# 51shiyanban.net
KiCad netlist of a schematic drawn in Altium Designer
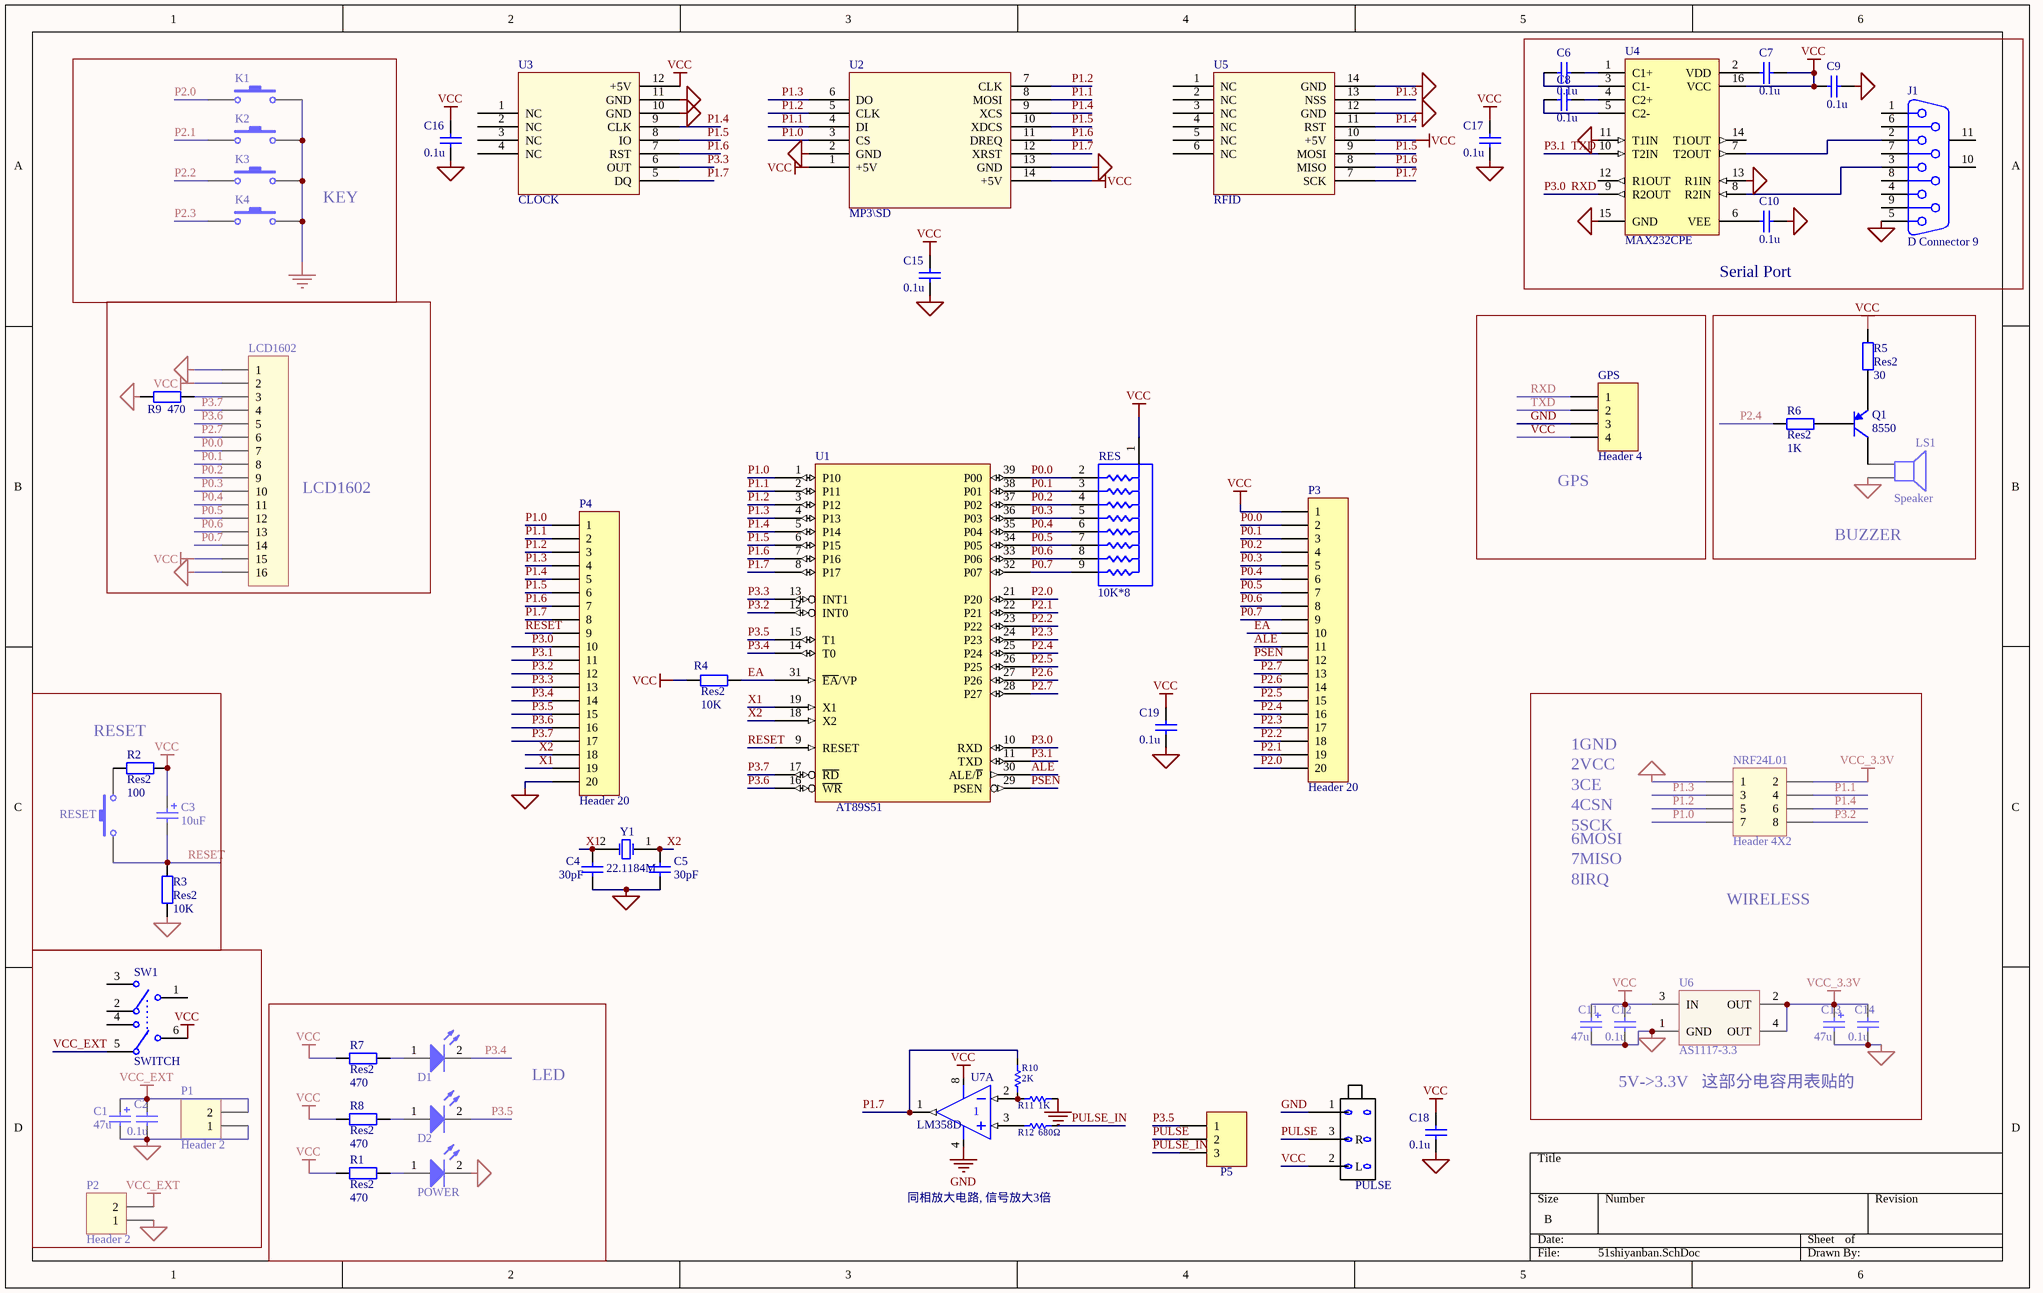
[diagram p0: 51shiyanban.SchDoc]

(export (version "E")
  (design (tool "Eeschema 10.0.6"))
  (components
    (comp (ref "C1")
      (value "47u")
      (footprint "CAP3_HT")
      (description "Polarized Capacitor (Radial)")
      (fields
        (field (name "MANUFACTURER") "Generic Components")
        (field (name "Comment") "Cap Pol1")
        (field (name "PUBLISHER") "Altium Hobart Technology Centre")
      )
      (libsource (lib "Miscellaneous Devices") (part "Cap Pol1"))
    )
    (comp (ref "C2")
      (value "0.1u")
      (footprint "CAP1_HT")
      (description "Capacitor")
      (fields
        (field (name "MANUFACTURER") "Generic Components")
        (field (name "PUBLISHER") "Altium Hobart Technology Centre")
      )
      (libsource (lib "") (part "Cap_1"))
    )
    (comp (ref "C3")
      (value "10uF")
      (footprint "CAP3_HT")
      (description "Polarized Capacitor (Radial)")
      (fields
        (field (name "MANUFACTURER") "Generic Components")
        (field (name "Comment") "Cap Pol1")
        (field (name "PUBLISHER") "Altium Hobart Technology Centre")
      )
      (libsource (lib "Miscellaneous Devices") (part "Cap Pol1"))
    )
    (comp (ref "C4")
      (value "30pF")
      (footprint "CAP1_HT")
      (description "Capacitor")
      (fields
        (field (name "MANUFACTURER") "Generic Components")
        (field (name "Comment") "30P")
        (field (name "PUBLISHER") "Altium Hobart Technology Centre")
      )
      (libsource (lib "") (part "Cap_1"))
    )
    (comp (ref "C5")
      (value "30pF")
      (footprint "CAP1_HT")
      (description "Capacitor")
      (fields
        (field (name "MANUFACTURER") "Generic Components")
        (field (name "Comment") "30P")
        (field (name "PUBLISHER") "Altium Hobart Technology Centre")
      )
      (libsource (lib "") (part "Cap_1"))
    )
    (comp (ref "C6")
      (value "0.1u")
      (footprint "CAP1_HT")
      (description "Capacitor")
      (fields
        (field (name "MANUFACTURER") "Generic Components")
        (field (name "PUBLISHER") "Altium Hobart Technology Centre")
      )
      (libsource (lib "Miscellaneous Devices") (part "Cap"))
    )
    (comp (ref "C7")
      (value "0.1u")
      (footprint "CAP1_HT")
      (description "Capacitor")
      (fields
        (field (name "MANUFACTURER") "Generic Components")
        (field (name "PUBLISHER") "Altium Hobart Technology Centre")
      )
      (libsource (lib "Miscellaneous Devices") (part "Cap"))
    )
    (comp (ref "C8")
      (value "0.1u")
      (footprint "CAP1_HT")
      (description "Capacitor")
      (fields
        (field (name "MANUFACTURER") "Generic Components")
        (field (name "PUBLISHER") "Altium Hobart Technology Centre")
      )
      (libsource (lib "Miscellaneous Devices") (part "Cap"))
    )
    (comp (ref "C9")
      (value "0.1u")
      (footprint "CAP1_HT")
      (description "Capacitor")
      (fields
        (field (name "MANUFACTURER") "Generic Components")
        (field (name "PUBLISHER") "Altium Hobart Technology Centre")
      )
      (libsource (lib "Miscellaneous Devices") (part "Cap"))
    )
    (comp (ref "C10")
      (value "0.1u")
      (footprint "CAP1_HT")
      (description "Capacitor")
      (fields
        (field (name "MANUFACTURER") "Generic Components")
        (field (name "PUBLISHER") "Altium Hobart Technology Centre")
      )
      (libsource (lib "Miscellaneous Devices") (part "Cap"))
    )
    (comp (ref "C11")
      (value "47u")
      (footprint "CAP_CA_D")
      (description "Polarized Capacitor (Radial)")
      (fields
        (field (name "MANUFACTURER") "Generic Components")
        (field (name "PUBLISHER") "Altium Hobart Technology Centre")
      )
      (libsource (lib "Miscellaneous Devices") (part "Cap Pol1"))
    )
    (comp (ref "C12")
      (value "0.1u")
      (footprint "C0805")
      (description "Capacitor")
      (fields
        (field (name "MANUFACTURER") "Generic Components")
        (field (name "PUBLISHER") "Altium Hobart Technology Centre")
      )
      (libsource (lib "") (part "Cap_1"))
    )
    (comp (ref "C13")
      (value "47u")
      (footprint "CAP_CA_D")
      (description "Polarized Capacitor (Radial)")
      (fields
        (field (name "MANUFACTURER") "Generic Components")
        (field (name "PUBLISHER") "Altium Hobart Technology Centre")
      )
      (libsource (lib "Miscellaneous Devices") (part "Cap Pol1"))
    )
    (comp (ref "C14")
      (value "0.1u")
      (footprint "C0805")
      (description "Capacitor")
      (fields
        (field (name "MANUFACTURER") "Generic Components")
        (field (name "PUBLISHER") "Altium Hobart Technology Centre")
      )
      (libsource (lib "") (part "Cap_1"))
    )
    (comp (ref "C15")
      (value "0.1u")
      (footprint "C0805")
      (description "Capacitor")
      (fields
        (field (name "MANUFACTURER") "Generic Components")
        (field (name "PUBLISHER") "Altium Hobart Technology Centre")
      )
      (libsource (lib "") (part "Cap_1"))
    )
    (comp (ref "C16")
      (value "0.1u")
      (footprint "C0805")
      (description "Capacitor")
      (fields
        (field (name "MANUFACTURER") "Generic Components")
        (field (name "PUBLISHER") "Altium Hobart Technology Centre")
      )
      (libsource (lib "") (part "Cap_1"))
    )
    (comp (ref "C17")
      (value "0.1u")
      (footprint "C0805")
      (description "Capacitor")
      (fields
        (field (name "MANUFACTURER") "Generic Components")
        (field (name "PUBLISHER") "Altium Hobart Technology Centre")
      )
      (libsource (lib "") (part "Cap_1"))
    )
    (comp (ref "C18")
      (value "0.1u")
      (footprint "C0805")
      (description "Capacitor")
      (fields
        (field (name "MANUFACTURER") "Generic Components")
        (field (name "PUBLISHER") "Altium Hobart Technology Centre")
      )
      (libsource (lib "") (part "Cap_1"))
    )
    (comp (ref "C19")
      (value "0.1u")
      (footprint "C0805")
      (description "Capacitor")
      (fields
        (field (name "MANUFACTURER") "Generic Components")
        (field (name "PUBLISHER") "Altium Hobart Technology Centre")
      )
      (libsource (lib "") (part "Cap_1"))
    )
    (comp (ref "D1")
      (value "LED0")
      (footprint "LED1_HT")
      (description "Typical INFRARED GaAs LED")
      (fields
        (field (name "MANUFACTURER") "Generic Components")
        (field (name "PUBLISHER") "Altium Hobart Technology Centre")
      )
      (libsource (lib "Miscellaneous Devices") (part "LED0"))
    )
    (comp (ref "D2")
      (value "LED0")
      (footprint "LED1_HT")
      (description "Typical INFRARED GaAs LED")
      (fields
        (field (name "MANUFACTURER") "Generic Components")
        (field (name "PUBLISHER") "Altium Hobart Technology Centre")
      )
      (libsource (lib "Miscellaneous Devices") (part "LED0"))
    )
    (comp (ref "GPS")
      (value "Header 4")
      (footprint "HDR1X4")
      (description "Header, 4-Pin")
      (fields (field (name "PUBLISHER") "Altium Limited"))
      (libsource (lib "Miscellaneous Connectors") (part "Header 4"))
    )
    (comp (ref "J1")
      (value "D Connector 9")
      (footprint "DSUB1.385-2H9")
      (description "Receptacle Assembly, 9 Position, Right Angle")
      (fields (field (name "PUBLISHER") "Altium Limited"))
      (libsource (lib "Miscellaneous Connectors") (part "D Connector 9"))
    )
    (comp (ref "K1")
      (value "~")
      (footprint "KEY1_HT")
      (description "Switch")
      (fields (field (name "MANUFACTURER") "Generic Components"))
      (libsource (lib "Miscellaneous Devices") (part "SW-PB"))
    )
    (comp (ref "K2")
      (value "~")
      (footprint "KEY1_HT")
      (description "Switch")
      (fields (field (name "MANUFACTURER") "Generic Components"))
      (libsource (lib "Miscellaneous Devices") (part "SW-PB"))
    )
    (comp (ref "K3")
      (value "~")
      (footprint "KEY1_HT")
      (description "Switch")
      (fields (field (name "MANUFACTURER") "Generic Components"))
      (libsource (lib "Miscellaneous Devices") (part "SW-PB"))
    )
    (comp (ref "K4")
      (value "~")
      (footprint "KEY1_HT")
      (description "Switch")
      (fields (field (name "MANUFACTURER") "Generic Components"))
      (libsource (lib "Miscellaneous Devices") (part "SW-PB"))
    )
    (comp (ref "LCD1602")
      (value "Header 16")
      (footprint "HDR1X16")
      (description "Header, 16-Pin")
      (fields (field (name "PUBLISHER") "Altium Limited"))
      (libsource (lib "Miscellaneous Connectors") (part "Header 16"))
    )
    (comp (ref "LS1")
      (value "Speaker")
      (footprint "BUZZER_HT")
      (description "Loudspeaker")
      (fields (field (name "MANUFACTURER") "Generic Components"))
      (libsource (lib "Miscellaneous Devices") (part "Speaker"))
    )
    (comp (ref "NRF24L01")
      (value "Header 4X2")
      (footprint "HDR2X4")
      (description "Header, 4-Pin, Dual row")
      (fields (field (name "PUBLISHER") "Altium Limited"))
      (libsource (lib "Miscellaneous Connectors") (part "Header 4X2"))
    )
    (comp (ref "P1")
      (value "Header 2")
      (footprint "DCJACK")
      (description "Header, 2-Pin")
      (fields (field (name "MANUFACTURER") "Generic Components"))
      (libsource (lib "Miscellaneous Connectors") (part "Header 2"))
    )
    (comp (ref "P2")
      (value "Header 2")
      (footprint "Power_small")
      (description "Header, 2-Pin")
      (fields (field (name "MANUFACTURER") "Generic Components"))
      (libsource (lib "Miscellaneous Connectors") (part "Header 2"))
    )
    (comp (ref "P3")
      (value "Header 20")
      (footprint "HDR1X20")
      (description "Header, 20-Pin")
      (fields (field (name "PUBLISHER") "Altium Limited"))
      (libsource (lib "Miscellaneous Connectors") (part "Header 20"))
    )
    (comp (ref "P4")
      (value "Header 20")
      (footprint "HDR1X20")
      (description "Header, 20-Pin")
      (fields (field (name "PUBLISHER") "Altium Limited"))
      (libsource (lib "Miscellaneous Connectors") (part "Header 20"))
    )
    (comp (ref "P5")
      (value "Header 3")
      (footprint "HDR1X3")
      (description "Header, 3-Pin")
      (fields (field (name "PUBLISHER") "Altium Limited"))
      (libsource (lib "Miscellaneous Connectors") (part "Header 3"))
    )
    (comp (ref "POWER")
      (value "LED0")
      (footprint "LED1_HT")
      (description "Typical INFRARED GaAs LED")
      (fields
        (field (name "MANUFACTURER") "Generic Components")
        (field (name "PUBLISHER") "Altium Hobart Technology Centre")
      )
      (libsource (lib "Miscellaneous Devices") (part "LED0"))
    )
    (comp (ref "PULSE")
      (value "Phonejack")
      (footprint "3.5mmphonejack")
      (libsource (lib "MyLib") (part "Phonejack"))
    )
    (comp (ref "Q1")
      (value "8550")
      (footprint "Transistor")
      (description "PNP General Purpose Amplifier")
      (fields (field (name "PUBLISHER") "Altium Limited"))
      (libsource (lib "Miscellaneous Devices") (part "2N3906"))
    )
    (comp (ref "R1")
      (value "Res2")
      (footprint "AXIAL-0.4")
      (description "Resistor")
      (fields (field (name "ALTIUM_VALUE") "470") (field (name "PUBLISHER") "Altium Limited"))
      (libsource (lib "Miscellaneous Devices") (part "Res2"))
    )
    (comp (ref "R2")
      (value "Res2")
      (footprint "AXIAL-0.4")
      (description "Resistor")
      (fields (field (name "ALTIUM_VALUE") "100") (field (name "PUBLISHER") "Altium Limited"))
      (libsource (lib "") (part "Res2_2"))
    )
    (comp (ref "R3")
      (value "Res2")
      (footprint "AXIAL-0.4")
      (description "Resistor")
      (fields (field (name "ALTIUM_VALUE") "10K") (field (name "PUBLISHER") "Altium Limited"))
      (libsource (lib "") (part "Res2_1"))
    )
    (comp (ref "R4")
      (value "Res2")
      (footprint "AXIAL-0.4")
      (description "Resistor")
      (fields (field (name "ALTIUM_VALUE") "10K") (field (name "PUBLISHER") "Altium Limited"))
      (libsource (lib "") (part "Res2_2"))
    )
    (comp (ref "R5")
      (value "Res2")
      (footprint "AXIAL-0.4")
      (description "Resistor")
      (fields (field (name "ALTIUM_VALUE") "30") (field (name "PUBLISHER") "Altium Limited"))
      (libsource (lib "") (part "Res2_3"))
    )
    (comp (ref "R6")
      (value "Res2")
      (footprint "AXIAL-0.4")
      (description "Resistor")
      (fields (field (name "ALTIUM_VALUE") "1K") (field (name "PUBLISHER") "Altium Limited"))
      (libsource (lib "") (part "Res2_2"))
    )
    (comp (ref "R7")
      (value "Res2")
      (footprint "AXIAL-0.4")
      (description "Resistor")
      (fields (field (name "ALTIUM_VALUE") "470") (field (name "PUBLISHER") "Altium Limited"))
      (libsource (lib "Miscellaneous Devices") (part "Res2"))
    )
    (comp (ref "R8")
      (value "Res2")
      (footprint "AXIAL-0.4")
      (description "Resistor")
      (fields (field (name "ALTIUM_VALUE") "470") (field (name "PUBLISHER") "Altium Limited"))
      (libsource (lib "Miscellaneous Devices") (part "Res2"))
    )
    (comp (ref "R9")
      (value "470")
      (footprint "AXIAL-0.4")
      (description "Resistor")
      (fields (field (name "Comment") "Res2") (field (name "PUBLISHER") "Altium Limited"))
      (libsource (lib "") (part "Res2_2"))
    )
    (comp (ref "R10")
      (value "2K")
      (footprint "C0805")
      (description "Resistor")
      (fields (field (name "PUBLISHER") "Altium Limited"))
      (libsource (lib "Miscellaneous Devices") (part "Res1"))
    )
    (comp (ref "R11")
      (value "1K")
      (footprint "C0805")
      (description "Resistor")
      (fields (field (name "PUBLISHER") "Altium Limited"))
      (libsource (lib "Miscellaneous Devices") (part "Res1"))
    )
    (comp (ref "R12")
      (value "680Ω")
      (footprint "C0805")
      (description "Resistor")
      (fields (field (name "PUBLISHER") "Altium Limited"))
      (libsource (lib "Miscellaneous Devices") (part "Res1"))
    )
    (comp (ref "RES") (value "10K*8") (footprint "RES3_HT") (libsource (lib "Schlib1") (part "RESPACK")))
    (comp (ref "RESET")
      (value "~")
      (footprint "KEY1_HT")
      (description "Switch")
      (fields (field (name "MANUFACTURER") "Generic Components"))
      (libsource (lib "Miscellaneous Devices") (part "SW-PB"))
    )
    (comp (ref "SW1") (value "SWITCH") (footprint "DPDT-6") (libsource (lib "WENSHI") (part "SW-DPDT")))
    (comp (ref "U1") (value "AT89S51") (footprint "KDIP40_HT") (libsource (lib "*") (part "8031")))
    (comp (ref "U2") (value "MP~{3}SD") (footprint "MP3SD") (libsource (lib "Schlib1") (part "MP3SD")))
    (comp (ref "U3") (value "CLOCK") (footprint "CLOCK") (libsource (lib "Schlib1") (part "CLOCK")))
    (comp (ref "U4")
      (value "MAX232CPE")
      (footprint "DIP-16")
      (description "+5V Powered RS-232 Driver/Receiver")
      (fields (field (name "PUBLISHER") "Altium Limited"))
      (libsource (lib "Maxim Communication Transceiver") (part "MAX232CPE"))
    )
    (comp (ref "U5") (value "RFID") (footprint "RFID") (libsource (lib "Schlib1") (part "RFID")))
    (comp (ref "U6")
      (value "AS1117-3.3")
      (footprint "SOT-223")
      (libsource (lib "WENSHI") (part "AS1117-3.3"))
    )
    (comp (ref "U7")
      (value "LM358D")
      (footprint "751-02_N")
      (description "Dual Low-Power Operational Amplifier")
      (fields (field (name "PUBLISHER") "Altium Limited"))
      (libsource (lib "Motorola Amplifier Operational Amplifier") (part "LM358D"))
    )
    (comp (ref "Y1")
      (value "22.1184M")
      (footprint "XTAL1_HT")
      (description "Crystal Oscillator")
      (fields
        (field (name "MANUFACTURER") "Generic Components")
        (field (name "PUBLISHER") "Altium Hobart Technology Centre")
      )
      (libsource (lib "Miscellaneous Devices") (part "XTAL"))
    )
  )
  (nets
    (net (code "1") (name "/ALE") (class "Default")
      (node (ref "P3") (pin "11") (pinfunction "11_11") (pintype "passive"))
      (node (ref "U1") (pin "30") (pinfunction "ALE/~{P}_30") (pintype "output"))
    )
    (net (code "2") (name "/EA") (class "Default")
      (node (ref "P3") (pin "10") (pinfunction "10_10") (pintype "passive"))
      (node (ref "R4") (pin "1") (pinfunction "1_1") (pintype "passive"))
      (node (ref "U1") (pin "31") (pinfunction "~{EA}/VP_31") (pintype "input"))
    )
    (net (code "3") (name "/P0.0") (class "Default")
      (node (ref "LCD1602") (pin "7") (pinfunction "7_7") (pintype "passive"))
      (node (ref "P3") (pin "2") (pinfunction "2_2") (pintype "passive"))
      (node (ref "RES") (pin "2") (pinfunction "2_2") (pintype "passive"))
      (node (ref "U1") (pin "39") (pinfunction "P00_39") (pintype "bidirectional"))
    )
    (net (code "4") (name "/P0.1") (class "Default")
      (node (ref "LCD1602") (pin "8") (pinfunction "8_8") (pintype "passive"))
      (node (ref "P3") (pin "3") (pinfunction "3_3") (pintype "passive"))
      (node (ref "RES") (pin "3") (pinfunction "3_3") (pintype "passive"))
      (node (ref "U1") (pin "38") (pinfunction "P01_38") (pintype "bidirectional"))
    )
    (net (code "5") (name "/P0.2") (class "Default")
      (node (ref "LCD1602") (pin "9") (pinfunction "9_9") (pintype "passive"))
      (node (ref "P3") (pin "4") (pinfunction "4_4") (pintype "passive"))
      (node (ref "RES") (pin "4") (pinfunction "4_4") (pintype "passive"))
      (node (ref "U1") (pin "37") (pinfunction "P02_37") (pintype "bidirectional"))
    )
    (net (code "6") (name "/P0.3") (class "Default")
      (node (ref "LCD1602") (pin "10") (pinfunction "10_10") (pintype "passive"))
      (node (ref "P3") (pin "5") (pinfunction "5_5") (pintype "passive"))
      (node (ref "RES") (pin "5") (pinfunction "5_5") (pintype "passive"))
      (node (ref "U1") (pin "36") (pinfunction "P03_36") (pintype "bidirectional"))
    )
    (net (code "7") (name "/P0.4") (class "Default")
      (node (ref "LCD1602") (pin "11") (pinfunction "11_11") (pintype "passive"))
      (node (ref "P3") (pin "6") (pinfunction "6_6") (pintype "passive"))
      (node (ref "RES") (pin "6") (pinfunction "6_6") (pintype "passive"))
      (node (ref "U1") (pin "35") (pinfunction "P04_35") (pintype "bidirectional"))
    )
    (net (code "8") (name "/P0.5") (class "Default")
      (node (ref "LCD1602") (pin "12") (pinfunction "12_12") (pintype "passive"))
      (node (ref "P3") (pin "7") (pinfunction "7_7") (pintype "passive"))
      (node (ref "RES") (pin "7") (pinfunction "7_7") (pintype "passive"))
      (node (ref "U1") (pin "34") (pinfunction "P05_34") (pintype "bidirectional"))
    )
    (net (code "9") (name "/P0.6") (class "Default")
      (node (ref "LCD1602") (pin "13") (pinfunction "13_13") (pintype "passive"))
      (node (ref "P3") (pin "8") (pinfunction "8_8") (pintype "passive"))
      (node (ref "RES") (pin "8") (pinfunction "8_8") (pintype "passive"))
      (node (ref "U1") (pin "33") (pinfunction "P06_33") (pintype "bidirectional"))
    )
    (net (code "10") (name "/P0.7") (class "Default")
      (node (ref "LCD1602") (pin "14") (pinfunction "14_14") (pintype "passive"))
      (node (ref "P3") (pin "9") (pinfunction "9_9") (pintype "passive"))
      (node (ref "RES") (pin "9") (pinfunction "9_9") (pintype "passive"))
      (node (ref "U1") (pin "32") (pinfunction "P07_32") (pintype "bidirectional"))
    )
    (net (code "11") (name "/P1.0") (class "Default")
      (node (ref "NRF24L01") (pin "7") (pinfunction "7_7") (pintype "passive"))
      (node (ref "P4") (pin "1") (pinfunction "1_1") (pintype "passive"))
      (node (ref "U1") (pin "1") (pinfunction "P10_1") (pintype "bidirectional"))
      (node (ref "U2") (pin "3") (pinfunction "CS_3") (pintype "passive"))
    )
    (net (code "12") (name "/P1.1") (class "Default")
      (node (ref "NRF24L01") (pin "4") (pinfunction "4_4") (pintype "passive"))
      (node (ref "P4") (pin "2") (pinfunction "2_2") (pintype "passive"))
      (node (ref "U1") (pin "2") (pinfunction "P11_2") (pintype "bidirectional"))
      (node (ref "U2") (pin "4") (pinfunction "DI_4") (pintype "passive"))
      (node (ref "U2") (pin "8") (pinfunction "MOSI_8") (pintype "passive"))
    )
    (net (code "13") (name "/P1.2") (class "Default")
      (node (ref "NRF24L01") (pin "5") (pinfunction "5_5") (pintype "passive"))
      (node (ref "P4") (pin "3") (pinfunction "3_3") (pintype "passive"))
      (node (ref "U1") (pin "3") (pinfunction "P12_3") (pintype "bidirectional"))
      (node (ref "U2") (pin "5") (pinfunction "CLK_5") (pintype "passive"))
      (node (ref "U2") (pin "7") (pinfunction "CLK_7") (pintype "passive"))
    )
    (net (code "14") (name "/P1.3") (class "Default")
      (node (ref "NRF24L01") (pin "3") (pinfunction "3_3") (pintype "passive"))
      (node (ref "P4") (pin "4") (pinfunction "4_4") (pintype "passive"))
      (node (ref "U1") (pin "4") (pinfunction "P13_4") (pintype "bidirectional"))
      (node (ref "U2") (pin "6") (pinfunction "DO_6") (pintype "passive"))
      (node (ref "U5") (pin "13") (pinfunction "NSS_13") (pintype "passive"))
    )
    (net (code "15") (name "/P1.4") (class "Default")
      (node (ref "NRF24L01") (pin "6") (pinfunction "6_6") (pintype "passive"))
      (node (ref "P4") (pin "5") (pinfunction "5_5") (pintype "passive"))
      (node (ref "U1") (pin "5") (pinfunction "P14_5") (pintype "bidirectional"))
      (node (ref "U2") (pin "9") (pinfunction "XCS_9") (pintype "passive"))
      (node (ref "U3") (pin "9") (pinfunction "CLK_9") (pintype "passive"))
      (node (ref "U5") (pin "11") (pinfunction "RST_11") (pintype "passive"))
    )
    (net (code "16") (name "/P1.5") (class "Default")
      (node (ref "P4") (pin "6") (pinfunction "6_6") (pintype "passive"))
      (node (ref "U1") (pin "6") (pinfunction "P15_6") (pintype "bidirectional"))
      (node (ref "U2") (pin "10") (pinfunction "XDCS_10") (pintype "passive"))
      (node (ref "U3") (pin "8") (pinfunction "IO_8") (pintype "passive"))
      (node (ref "U5") (pin "9") (pinfunction "MOSI_9") (pintype "passive"))
    )
    (net (code "17") (name "/P1.6") (class "Default")
      (node (ref "P4") (pin "7") (pinfunction "7_7") (pintype "passive"))
      (node (ref "U1") (pin "7") (pinfunction "P16_7") (pintype "bidirectional"))
      (node (ref "U2") (pin "11") (pinfunction "DREQ_11") (pintype "passive"))
      (node (ref "U3") (pin "7") (pinfunction "RST_7") (pintype "passive"))
      (node (ref "U5") (pin "8") (pinfunction "MISO_8") (pintype "passive"))
    )
    (net (code "18") (name "/P1.7") (class "Default")
      (node (ref "P4") (pin "8") (pinfunction "8_8") (pintype "passive"))
      (node (ref "R10") (pin "2") (pinfunction "2_2") (pintype "passive"))
      (node (ref "U1") (pin "8") (pinfunction "P17_8") (pintype "bidirectional"))
      (node (ref "U2") (pin "12") (pinfunction "XRST_12") (pintype "passive"))
      (node (ref "U3") (pin "5") (pinfunction "DQ_5") (pintype "passive"))
      (node (ref "U5") (pin "7") (pinfunction "SCK_7") (pintype "passive"))
      (node (ref "U7") (pin "1") (pinfunction "OUT_1") (pintype "output"))
    )
    (net (code "19") (name "/P2.0") (class "Default")
      (node (ref "K1") (pin "1") (pinfunction "1_1") (pintype "passive"))
      (node (ref "P3") (pin "20") (pinfunction "20_20") (pintype "passive"))
      (node (ref "U1") (pin "21") (pinfunction "P20_21") (pintype "bidirectional"))
    )
    (net (code "20") (name "/P2.1") (class "Default")
      (node (ref "K2") (pin "1") (pinfunction "1_1") (pintype "passive"))
      (node (ref "P3") (pin "19") (pinfunction "19_19") (pintype "passive"))
      (node (ref "U1") (pin "22") (pinfunction "P21_22") (pintype "bidirectional"))
    )
    (net (code "21") (name "/P2.2") (class "Default")
      (node (ref "K3") (pin "1") (pinfunction "1_1") (pintype "passive"))
      (node (ref "P3") (pin "18") (pinfunction "18_18") (pintype "passive"))
      (node (ref "U1") (pin "23") (pinfunction "P22_23") (pintype "bidirectional"))
    )
    (net (code "22") (name "/P2.3") (class "Default")
      (node (ref "K4") (pin "1") (pinfunction "1_1") (pintype "passive"))
      (node (ref "P3") (pin "17") (pinfunction "17_17") (pintype "passive"))
      (node (ref "U1") (pin "24") (pinfunction "P23_24") (pintype "bidirectional"))
    )
    (net (code "23") (name "/P2.4") (class "Default")
      (node (ref "P3") (pin "16") (pinfunction "16_16") (pintype "passive"))
      (node (ref "R6") (pin "2") (pinfunction "2_2") (pintype "passive"))
      (node (ref "U1") (pin "25") (pinfunction "P24_25") (pintype "bidirectional"))
    )
    (net (code "24") (name "/P2.5") (class "Default")
      (node (ref "P3") (pin "15") (pinfunction "15_15") (pintype "passive"))
      (node (ref "U1") (pin "26") (pinfunction "P25_26") (pintype "bidirectional"))
    )
    (net (code "25") (name "/P2.6") (class "Default")
      (node (ref "P3") (pin "14") (pinfunction "14_14") (pintype "passive"))
      (node (ref "U1") (pin "27") (pinfunction "P26_27") (pintype "bidirectional"))
    )
    (net (code "26") (name "/P2.7") (class "Default")
      (node (ref "LCD1602") (pin "6") (pinfunction "6_6") (pintype "passive"))
      (node (ref "P3") (pin "13") (pinfunction "13_13") (pintype "passive"))
      (node (ref "U1") (pin "28") (pinfunction "P27_28") (pintype "bidirectional"))
    )
    (net (code "27") (name "/P3.0") (class "Default")
      (node (ref "GPS") (pin "1") (pinfunction "1_1") (pintype "passive"))
      (node (ref "P4") (pin "10") (pinfunction "10_10") (pintype "passive"))
      (node (ref "U1") (pin "10") (pinfunction "RXD_10") (pintype "bidirectional"))
      (node (ref "U4") (pin "9") (pinfunction "R2OUT_9") (pintype "output"))
    )
    (net (code "28") (name "/P3.1") (class "Default")
      (node (ref "GPS") (pin "2") (pinfunction "2_2") (pintype "passive"))
      (node (ref "P4") (pin "11") (pinfunction "11_11") (pintype "passive"))
      (node (ref "U1") (pin "11") (pinfunction "TXD_11") (pintype "bidirectional"))
      (node (ref "U4") (pin "10") (pinfunction "T2IN_10") (pintype "input"))
    )
    (net (code "29") (name "/P3.2") (class "Default")
      (node (ref "NRF24L01") (pin "8") (pinfunction "8_8") (pintype "passive"))
      (node (ref "P4") (pin "12") (pinfunction "12_12") (pintype "passive"))
      (node (ref "U1") (pin "12") (pinfunction "INT0_12") (pintype "bidirectional"))
    )
    (net (code "30") (name "/P3.3") (class "Default")
      (node (ref "P4") (pin "13") (pinfunction "13_13") (pintype "passive"))
      (node (ref "U1") (pin "13") (pinfunction "INT1_13") (pintype "bidirectional"))
      (node (ref "U3") (pin "6") (pinfunction "OUT_6") (pintype "passive"))
    )
    (net (code "31") (name "/P3.4") (class "Default")
      (node (ref "D1") (pin "2") (pinfunction "K_2") (pintype "passive"))
      (node (ref "P4") (pin "14") (pinfunction "14_14") (pintype "passive"))
      (node (ref "U1") (pin "14") (pinfunction "T0_14") (pintype "bidirectional"))
    )
    (net (code "32") (name "/P3.5") (class "Default")
      (node (ref "D2") (pin "2") (pinfunction "K_2") (pintype "passive"))
      (node (ref "P4") (pin "15") (pinfunction "15_15") (pintype "passive"))
      (node (ref "P5") (pin "1") (pinfunction "1_1") (pintype "passive"))
      (node (ref "U1") (pin "15") (pinfunction "T1_15") (pintype "bidirectional"))
    )
    (net (code "33") (name "/P3.6") (class "Default")
      (node (ref "LCD1602") (pin "5") (pinfunction "5_5") (pintype "passive"))
      (node (ref "P4") (pin "16") (pinfunction "16_16") (pintype "passive"))
      (node (ref "U1") (pin "16") (pinfunction "~{WR}_16") (pintype "bidirectional"))
    )
    (net (code "34") (name "/P3.7") (class "Default")
      (node (ref "LCD1602") (pin "4") (pinfunction "4_4") (pintype "passive"))
      (node (ref "P4") (pin "17") (pinfunction "17_17") (pintype "passive"))
      (node (ref "U1") (pin "17") (pinfunction "~{RD}_17") (pintype "bidirectional"))
    )
    (net (code "35") (name "/PSEN") (class "Default")
      (node (ref "P3") (pin "12") (pinfunction "12_12") (pintype "passive"))
      (node (ref "U1") (pin "29") (pinfunction "PSEN_29") (pintype "output"))
    )
    (net (code "36") (name "/PULSE") (class "Default")
      (node (ref "P5") (pin "2") (pinfunction "2_2") (pintype "passive"))
      (node (ref "PULSE") (pin "3") (pinfunction "R_3") (pintype "passive"))
    )
    (net (code "37") (name "/PULSE_IN") (class "Default")
      (node (ref "P5") (pin "3") (pinfunction "3_3") (pintype "passive"))
      (node (ref "R12") (pin "2") (pinfunction "2_2") (pintype "passive"))
    )
    (net (code "38") (name "/RESET") (class "Default")
      (node (ref "C3") (pin "2") (pinfunction "2_2") (pintype "passive"))
      (node (ref "P4") (pin "9") (pinfunction "9_9") (pintype "passive"))
      (node (ref "R3") (pin "2") (pinfunction "2_2") (pintype "passive"))
      (node (ref "RESET") (pin "1") (pinfunction "1_1") (pintype "passive"))
      (node (ref "U1") (pin "9") (pinfunction "RESET_9") (pintype "input"))
    )
    (net (code "39") (name "/X1") (class "Default")
      (node (ref "C4") (pin "1") (pinfunction "1_1") (pintype "passive"))
      (node (ref "P4") (pin "19") (pinfunction "19_19") (pintype "passive"))
      (node (ref "U1") (pin "19") (pinfunction "X1_19") (pintype "input"))
      (node (ref "Y1") (pin "2") (pinfunction "OSC2_2") (pintype "passive"))
    )
    (net (code "40") (name "/X2") (class "Default")
      (node (ref "C5") (pin "1") (pinfunction "1_1") (pintype "passive"))
      (node (ref "P4") (pin "18") (pinfunction "18_18") (pintype "passive"))
      (node (ref "U1") (pin "18") (pinfunction "X2_18") (pintype "input"))
      (node (ref "Y1") (pin "1") (pinfunction "OSC1_1") (pintype "passive"))
    )
    (net (code "41") (name "GND") (class "Default")
      (node (ref "C1") (pin "2") (pinfunction "2_2") (pintype "passive"))
      (node (ref "C10") (pin "2") (pinfunction "2_2") (pintype "passive"))
      (node (ref "C11") (pin "2") (pinfunction "2_2") (pintype "passive"))
      (node (ref "C12") (pin "2") (pinfunction "2_2") (pintype "passive"))
      (node (ref "C13") (pin "2") (pinfunction "2_2") (pintype "passive"))
      (node (ref "C14") (pin "2") (pinfunction "2_2") (pintype "passive"))
      (node (ref "C15") (pin "2") (pinfunction "2_2") (pintype "passive"))
      (node (ref "C16") (pin "2") (pinfunction "2_2") (pintype "passive"))
      (node (ref "C17") (pin "2") (pinfunction "2_2") (pintype "passive"))
      (node (ref "C18") (pin "2") (pinfunction "2_2") (pintype "passive"))
      (node (ref "C19") (pin "2") (pinfunction "2_2") (pintype "passive"))
      (node (ref "C2") (pin "2") (pinfunction "2_2") (pintype "passive"))
      (node (ref "C4") (pin "2") (pinfunction "2_2") (pintype "passive"))
      (node (ref "C5") (pin "2") (pinfunction "2_2") (pintype "passive"))
      (node (ref "C9") (pin "2") (pinfunction "2_2") (pintype "passive"))
      (node (ref "GPS") (pin "3") (pinfunction "3_3") (pintype "passive"))
      (node (ref "J1") (pin "5") (pinfunction "5_5") (pintype "passive"))
      (node (ref "K1") (pin "2") (pinfunction "2_2") (pintype "passive"))
      (node (ref "K2") (pin "2") (pinfunction "2_2") (pintype "passive"))
      (node (ref "K3") (pin "2") (pinfunction "2_2") (pintype "passive"))
      (node (ref "K4") (pin "2") (pinfunction "2_2") (pintype "passive"))
      (node (ref "LCD1602") (pin "1") (pinfunction "1_1") (pintype "passive"))
      (node (ref "LCD1602") (pin "16") (pinfunction "16_16") (pintype "passive"))
      (node (ref "LS1") (pin "2") (pinfunction "2_2") (pintype "passive"))
      (node (ref "NRF24L01") (pin "1") (pinfunction "1_1") (pintype "passive"))
      (node (ref "P1") (pin "1") (pinfunction "1_1") (pintype "passive"))
      (node (ref "P2") (pin "1") (pinfunction "1_1") (pintype "passive"))
      (node (ref "P4") (pin "20") (pinfunction "20_20") (pintype "passive"))
      (node (ref "POWER") (pin "2") (pinfunction "K_2") (pintype "passive"))
      (node (ref "PULSE") (pin "1") (pinfunction "GBUF_1") (pintype "passive"))
      (node (ref "R11") (pin "2") (pinfunction "2_2") (pintype "passive"))
      (node (ref "R3") (pin "1") (pinfunction "1_1") (pintype "passive"))
      (node (ref "R9") (pin "2") (pinfunction "2_2") (pintype "passive"))
      (node (ref "U1") (pin "20") (pinfunction "GND_20") (pintype "power_in"))
      (node (ref "U2") (pin "13") (pinfunction "GND_13") (pintype "passive"))
      (node (ref "U2") (pin "2") (pinfunction "GND_2") (pintype "passive"))
      (node (ref "U3") (pin "10") (pinfunction "GND_10") (pintype "passive"))
      (node (ref "U3") (pin "11") (pinfunction "GND_11") (pintype "passive"))
      (node (ref "U4") (pin "11") (pinfunction "T1IN_11") (pintype "input"))
      (node (ref "U4") (pin "13") (pinfunction "R1IN_13") (pintype "input"))
      (node (ref "U4") (pin "15") (pinfunction "GND_15") (pintype "power_in"))
      (node (ref "U5") (pin "12") (pinfunction "GND_12") (pintype "passive"))
      (node (ref "U5") (pin "14") (pinfunction "GND_14") (pintype "passive"))
      (node (ref "U6") (pin "1") (pinfunction "GND_1") (pintype "passive"))
      (node (ref "U7") (pin "4") (pinfunction "V-_4") (pintype "power_in"))
    )
    (net (code "42") (name "Net-(D1-A)") (class "Default")
      (node (ref "D1") (pin "1") (pinfunction "A_1") (pintype "passive"))
      (node (ref "R7") (pin "2") (pinfunction "2_2") (pintype "passive"))
    )
    (net (code "43") (name "Net-(D2-A)") (class "Default")
      (node (ref "D2") (pin "1") (pinfunction "A_1") (pintype "passive"))
      (node (ref "R8") (pin "2") (pinfunction "2_2") (pintype "passive"))
    )
    (net (code "44") (name "Net-(LCD1602-Pad3)") (class "Default")
      (node (ref "LCD1602") (pin "3") (pinfunction "3_3") (pintype "passive"))
      (node (ref "R9") (pin "1") (pinfunction "1_1") (pintype "passive"))
    )
    (net (code "45") (name "Net-(POWER-A)") (class "Default")
      (node (ref "POWER") (pin "1") (pinfunction "A_1") (pintype "passive"))
      (node (ref "R1") (pin "2") (pinfunction "2_2") (pintype "passive"))
    )
    (net (code "46") (name "Net-(Q1-B)") (class "Default")
      (node (ref "Q1") (pin "2") (pinfunction "B_2") (pintype "passive"))
      (node (ref "R6") (pin "1") (pinfunction "1_1") (pintype "passive"))
    )
    (net (code "47") (name "Net-(Q1-C)") (class "Default")
      (node (ref "LS1") (pin "1") (pinfunction "1_1") (pintype "passive"))
      (node (ref "Q1") (pin "3") (pinfunction "C_3") (pintype "passive"))
    )
    (net (code "48") (name "Net-(Q1-E)") (class "Default")
      (node (ref "Q1") (pin "1") (pinfunction "E_1") (pintype "passive"))
      (node (ref "R5") (pin "2") (pinfunction "2_2") (pintype "passive"))
    )
    (net (code "49") (name "Net-(R2-Pad2)") (class "Default")
      (node (ref "R2") (pin "2") (pinfunction "2_2") (pintype "passive"))
      (node (ref "RESET") (pin "2") (pinfunction "2_2") (pintype "passive"))
    )
    (net (code "50") (name "Net-(U4-C1+)") (class "Default")
      (node (ref "C6") (pin "2") (pinfunction "2_2") (pintype "passive"))
      (node (ref "U4") (pin "1") (pinfunction "C1+_1") (pintype "passive"))
    )
    (net (code "51") (name "Net-(U4-C1-)") (class "Default")
      (node (ref "C6") (pin "1") (pinfunction "1_1") (pintype "passive"))
      (node (ref "U4") (pin "3") (pinfunction "C1-_3") (pintype "passive"))
    )
    (net (code "52") (name "Net-(U4-C2+)") (class "Default")
      (node (ref "C8") (pin "2") (pinfunction "2_2") (pintype "passive"))
      (node (ref "U4") (pin "4") (pinfunction "C2+_4") (pintype "passive"))
    )
    (net (code "53") (name "Net-(U4-C2-)") (class "Default")
      (node (ref "C8") (pin "1") (pinfunction "1_1") (pintype "passive"))
      (node (ref "U4") (pin "5") (pinfunction "C2-_5") (pintype "passive"))
    )
    (net (code "54") (name "Net-(U4-R2IN)") (class "Default")
      (node (ref "J1") (pin "3") (pinfunction "3_3") (pintype "passive"))
      (node (ref "U4") (pin "8") (pinfunction "R2IN_8") (pintype "input"))
    )
    (net (code "55") (name "Net-(U4-T2OUT)") (class "Default")
      (node (ref "J1") (pin "2") (pinfunction "2_2") (pintype "passive"))
      (node (ref "U4") (pin "7") (pinfunction "T2OUT_7") (pintype "output"))
    )
    (net (code "56") (name "Net-(U4-VDD)") (class "Default")
      (node (ref "C7") (pin "1") (pinfunction "1_1") (pintype "passive"))
      (node (ref "U4") (pin "2") (pinfunction "VDD_2") (pintype "power_in"))
    )
    (net (code "57") (name "Net-(U4-VEE)") (class "Default")
      (node (ref "C10") (pin "1") (pinfunction "1_1") (pintype "passive"))
      (node (ref "U4") (pin "6") (pinfunction "VEE_6") (pintype "power_in"))
    )
    (net (code "58") (name "Net-(U7A-IN+)") (class "Default")
      (node (ref "R12") (pin "1") (pinfunction "1_1") (pintype "passive"))
      (node (ref "U7") (pin "3") (pinfunction "IN+_3") (pintype "input"))
    )
    (net (code "59") (name "Net-(U7A-IN-)") (class "Default")
      (node (ref "R10") (pin "1") (pinfunction "1_1") (pintype "passive"))
      (node (ref "R11") (pin "1") (pinfunction "1_1") (pintype "passive"))
      (node (ref "U7") (pin "2") (pinfunction "IN-_2") (pintype "input"))
    )
    (net (code "60") (name "VCC") (class "Default")
      (node (ref "C11") (pin "1") (pinfunction "1_1") (pintype "passive"))
      (node (ref "C12") (pin "1") (pinfunction "1_1") (pintype "passive"))
      (node (ref "C15") (pin "1") (pinfunction "1_1") (pintype "passive"))
      (node (ref "C16") (pin "1") (pinfunction "1_1") (pintype "passive"))
      (node (ref "C17") (pin "1") (pinfunction "1_1") (pintype "passive"))
      (node (ref "C18") (pin "1") (pinfunction "1_1") (pintype "passive"))
      (node (ref "C19") (pin "1") (pinfunction "1_1") (pintype "passive"))
      (node (ref "C3") (pin "1") (pinfunction "1_1") (pintype "passive"))
      (node (ref "C7") (pin "2") (pinfunction "2_2") (pintype "passive"))
      (node (ref "C9") (pin "1") (pinfunction "1_1") (pintype "passive"))
      (node (ref "GPS") (pin "4") (pinfunction "4_4") (pintype "passive"))
      (node (ref "LCD1602") (pin "15") (pinfunction "15_15") (pintype "passive"))
      (node (ref "LCD1602") (pin "2") (pinfunction "2_2") (pintype "passive"))
      (node (ref "P3") (pin "1") (pinfunction "1_1") (pintype "passive"))
      (node (ref "PULSE") (pin "2") (pinfunction "L_2") (pintype "passive"))
      (node (ref "R1") (pin "1") (pinfunction "1_1") (pintype "passive"))
      (node (ref "R2") (pin "1") (pinfunction "1_1") (pintype "passive"))
      (node (ref "R4") (pin "2") (pinfunction "2_2") (pintype "passive"))
      (node (ref "R5") (pin "1") (pinfunction "1_1") (pintype "passive"))
      (node (ref "R7") (pin "1") (pinfunction "1_1") (pintype "passive"))
      (node (ref "R8") (pin "1") (pinfunction "1_1") (pintype "passive"))
      (node (ref "RES") (pin "1") (pinfunction "1_1") (pintype "passive"))
      (node (ref "SW1") (pin "6") (pinfunction "6_6") (pintype "passive"))
      (node (ref "U1") (pin "40") (pinfunction "VCC_40") (pintype "power_in"))
      (node (ref "U2") (pin "1") (pinfunction "+5V_1") (pintype "passive"))
      (node (ref "U2") (pin "14") (pinfunction "+5V_14") (pintype "passive"))
      (node (ref "U3") (pin "12") (pinfunction "+5V_12") (pintype "passive"))
      (node (ref "U4") (pin "16") (pinfunction "VCC_16") (pintype "power_in"))
      (node (ref "U5") (pin "10") (pinfunction "+5V_10") (pintype "passive"))
      (node (ref "U6") (pin "3") (pinfunction "IN_3") (pintype "passive"))
      (node (ref "U7") (pin "8") (pinfunction "V+_8") (pintype "power_in"))
    )
    (net (code "61") (name "VCC_3.3V") (class "Default")
      (node (ref "C13") (pin "1") (pinfunction "1_1") (pintype "passive"))
      (node (ref "C14") (pin "1") (pinfunction "1_1") (pintype "passive"))
      (node (ref "NRF24L01") (pin "2") (pinfunction "2_2") (pintype "passive"))
      (node (ref "U6") (pin "2") (pinfunction "OUT_2") (pintype "passive"))
      (node (ref "U6") (pin "4") (pinfunction "OUT_4") (pintype "passive"))
    )
    (net (code "62") (name "VCC_EXT") (class "Default")
      (node (ref "C1") (pin "1") (pinfunction "1_1") (pintype "passive"))
      (node (ref "C2") (pin "1") (pinfunction "1_1") (pintype "passive"))
      (node (ref "P1") (pin "2") (pinfunction "2_2") (pintype "passive"))
      (node (ref "P2") (pin "2") (pinfunction "2_2") (pintype "passive"))
      (node (ref "SW1") (pin "5") (pinfunction "5_5") (pintype "passive"))
    )
    (net (code "63") (name "unconnected-(J1-MH1-Pad10)") (class "Default")
      (node (ref "J1") (pin "10") (pinfunction "MH1_10") (pintype "passive"))
    )
    (net (code "64") (name "unconnected-(J1-MH2-Pad11)") (class "Default")
      (node (ref "J1") (pin "11") (pinfunction "MH2_11") (pintype "passive"))
    )
    (net (code "65") (name "unconnected-(J1-Pad1)") (class "Default")
      (node (ref "J1") (pin "1") (pinfunction "1_1") (pintype "passive"))
    )
    (net (code "66") (name "unconnected-(J1-Pad4)") (class "Default")
      (node (ref "J1") (pin "4") (pinfunction "4_4") (pintype "passive"))
    )
    (net (code "67") (name "unconnected-(J1-Pad6)") (class "Default")
      (node (ref "J1") (pin "6") (pinfunction "6_6") (pintype "passive"))
    )
    (net (code "68") (name "unconnected-(J1-Pad7)") (class "Default")
      (node (ref "J1") (pin "7") (pinfunction "7_7") (pintype "passive"))
    )
    (net (code "69") (name "unconnected-(J1-Pad8)") (class "Default")
      (node (ref "J1") (pin "8") (pinfunction "8_8") (pintype "passive"))
    )
    (net (code "70") (name "unconnected-(J1-Pad9)") (class "Default")
      (node (ref "J1") (pin "9") (pinfunction "9_9") (pintype "passive"))
    )
    (net (code "71") (name "unconnected-(SW1-Pad1)") (class "Default")
      (node (ref "SW1") (pin "1") (pinfunction "1_1") (pintype "passive"))
    )
    (net (code "72") (name "unconnected-(SW1-Pad2)") (class "Default")
      (node (ref "SW1") (pin "2") (pinfunction "2_2") (pintype "passive"))
    )
    (net (code "73") (name "unconnected-(SW1-Pad3)") (class "Default")
      (node (ref "SW1") (pin "3") (pinfunction "3_3") (pintype "passive"))
    )
    (net (code "74") (name "unconnected-(SW1-Pad4)") (class "Default")
      (node (ref "SW1") (pin "4") (pinfunction "4_4") (pintype "passive"))
    )
    (net (code "75") (name "unconnected-(U3-NC-Pad1)") (class "Default")
      (node (ref "U3") (pin "1") (pinfunction "NC_1") (pintype "passive"))
    )
    (net (code "76") (name "unconnected-(U3-NC-Pad2)") (class "Default")
      (node (ref "U3") (pin "2") (pinfunction "NC_2") (pintype "passive"))
    )
    (net (code "77") (name "unconnected-(U3-NC-Pad3)") (class "Default")
      (node (ref "U3") (pin "3") (pinfunction "NC_3") (pintype "passive"))
    )
    (net (code "78") (name "unconnected-(U3-NC-Pad4)") (class "Default")
      (node (ref "U3") (pin "4") (pinfunction "NC_4") (pintype "passive"))
    )
    (net (code "79") (name "unconnected-(U4-R1OUT-Pad12)") (class "Default")
      (node (ref "U4") (pin "12") (pinfunction "R1OUT_12") (pintype "output"))
    )
    (net (code "80") (name "unconnected-(U4-T1OUT-Pad14)") (class "Default")
      (node (ref "U4") (pin "14") (pinfunction "T1OUT_14") (pintype "output"))
    )
    (net (code "81") (name "unconnected-(U5-NC-Pad1)") (class "Default")
      (node (ref "U5") (pin "1") (pinfunction "NC_1") (pintype "passive"))
    )
    (net (code "82") (name "unconnected-(U5-NC-Pad2)") (class "Default")
      (node (ref "U5") (pin "2") (pinfunction "NC_2") (pintype "passive"))
    )
    (net (code "83") (name "unconnected-(U5-NC-Pad3)") (class "Default")
      (node (ref "U5") (pin "3") (pinfunction "NC_3") (pintype "passive"))
    )
    (net (code "84") (name "unconnected-(U5-NC-Pad4)") (class "Default")
      (node (ref "U5") (pin "4") (pinfunction "NC_4") (pintype "passive"))
    )
    (net (code "85") (name "unconnected-(U5-NC-Pad5)") (class "Default")
      (node (ref "U5") (pin "5") (pinfunction "NC_5") (pintype "passive"))
    )
    (net (code "86") (name "unconnected-(U5-NC-Pad6)") (class "Default")
      (node (ref "U5") (pin "6") (pinfunction "NC_6") (pintype "passive"))
    )
  )
)
